# ADC_INPUT_BIAS.net
KiCad netlist of a schematic drawn in Altium Designer
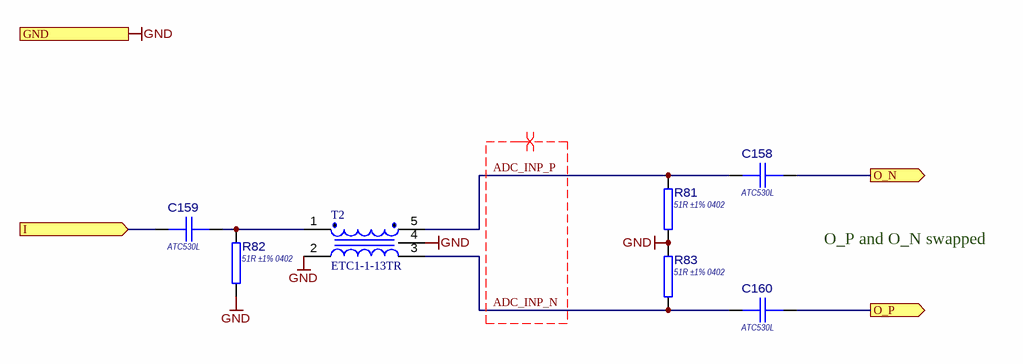
[diagram p0: ADC_INPUT_BIAS.SchDoc]

(export (version "E")
  (design (tool "Eeschema 10.0.6"))
  (components
    (comp (ref "C158")
      (value "ATC530L")
      (footprint "CAPC1005X06L")
      (description "100n 16V ±15% 0402 (1005 metric) ATC530L104KT16T")
      (fields (field (name "TOLERANCE") "±15%"))
      (libsource (lib "Omnisys Vault") (part "CAP-2PIN"))
    )
    (comp (ref "C159")
      (value "ATC530L")
      (footprint "CAPC1005X06L")
      (description "100n 16V ±15% 0402 (1005 metric) ATC530L104KT16T")
      (fields (field (name "TOLERANCE") "±15%"))
      (libsource (lib "Omnisys Vault") (part "CAP-2PIN"))
    )
    (comp (ref "C160")
      (value "ATC530L")
      (footprint "CAPC1005X06L")
      (description "100n 16V ±15% 0402 (1005 metric) ATC530L104KT16T")
      (fields (field (name "TOLERANCE") "±15%"))
      (libsource (lib "Omnisys Vault") (part "CAP-2PIN"))
    )
    (comp (ref "R81")
      (value "51R ±1% 0402")
      (footprint "RESC1005L")
      (description "51R ±1% ±100 ppm/˚C 0.05W 50V 0402 (1005 metric)")
      (fields (field (name "POWER") "0.10W") (field (name "TOLERANCE") "1"))
      (libsource (lib "Omnisys Vault") (part "RES-2PIN"))
    )
    (comp (ref "R82")
      (value "51R ±1% 0402")
      (footprint "RESC1005L")
      (description "51R ±1% ±100 ppm/˚C 0.05W 50V 0402 (1005 metric)")
      (fields (field (name "POWER") "0.10W") (field (name "TOLERANCE") "1"))
      (libsource (lib "Omnisys Vault") (part "RES-2PIN"))
    )
    (comp (ref "R83")
      (value "51R ±1% 0402")
      (footprint "RESC1005L")
      (description "51R ±1% ±100 ppm/˚C 0.05W 50V 0402 (1005 metric)")
      (fields (field (name "POWER") "0.10W") (field (name "TOLERANCE") "1"))
      (libsource (lib "Omnisys Vault") (part "RES-2PIN"))
    )
    (comp (ref "T2")
      (value "ETC1-1-13TR")
      (footprint "SOTFL50P160X73-3N")
      (description "Transformers Audio & Signal 4.5-3000MHz IL 2dB Impedance Ratio 1:1")
      (libsource (lib "Omnisys Vault") (part "ETC1-1-13TR"))
    )
  )
  (nets
    (net (code "1") (name "/ADC_INP_N") (class "Default")
      (node (ref "C160") (pin "2") (pinfunction "2_2") (pintype "passive"))
      (node (ref "R83") (pin "1") (pinfunction "1_1") (pintype "passive"))
      (node (ref "T2") (pin "3") (pinfunction "Secondary_3") (pintype "passive"))
    )
    (net (code "2") (name "/ADC_INP_P") (class "Default")
      (node (ref "C158") (pin "2") (pinfunction "2_2") (pintype "passive"))
      (node (ref "R81") (pin "2") (pinfunction "2_2") (pintype "passive"))
      (node (ref "T2") (pin "5") (pinfunction "Secondary_dot_5") (pintype "passive"))
    )
    (net (code "3") (name "/I") (class "Default")
      (node (ref "C159") (pin "2") (pinfunction "2_2") (pintype "passive"))
    )
    (net (code "4") (name "/O_N") (class "Default")
      (node (ref "C158") (pin "1") (pinfunction "1_1") (pintype "passive"))
    )
    (net (code "5") (name "/O_P") (class "Default")
      (node (ref "C160") (pin "1") (pinfunction "1_1") (pintype "passive"))
    )
    (net (code "6") (name "GND") (class "Default")
      (node (ref "R81") (pin "1") (pinfunction "1_1") (pintype "passive"))
      (node (ref "R82") (pin "2") (pinfunction "2_2") (pintype "passive"))
      (node (ref "R83") (pin "2") (pinfunction "2_2") (pintype "passive"))
      (node (ref "T2") (pin "2") (pinfunction "Primary_2") (pintype "passive"))
      (node (ref "T2") (pin "4") (pinfunction "NC_4") (pintype "passive"))
    )
    (net (code "7") (name "Net-(T2-Primary_dot)") (class "Default")
      (node (ref "C159") (pin "1") (pinfunction "1_1") (pintype "passive"))
      (node (ref "R82") (pin "1") (pinfunction "1_1") (pintype "passive"))
      (node (ref "T2") (pin "1") (pinfunction "Primary_dot_1") (pintype "passive"))
    )
  )
)
